# Sheet1.net
KiCad netlist of a schematic drawn in Altium Designer
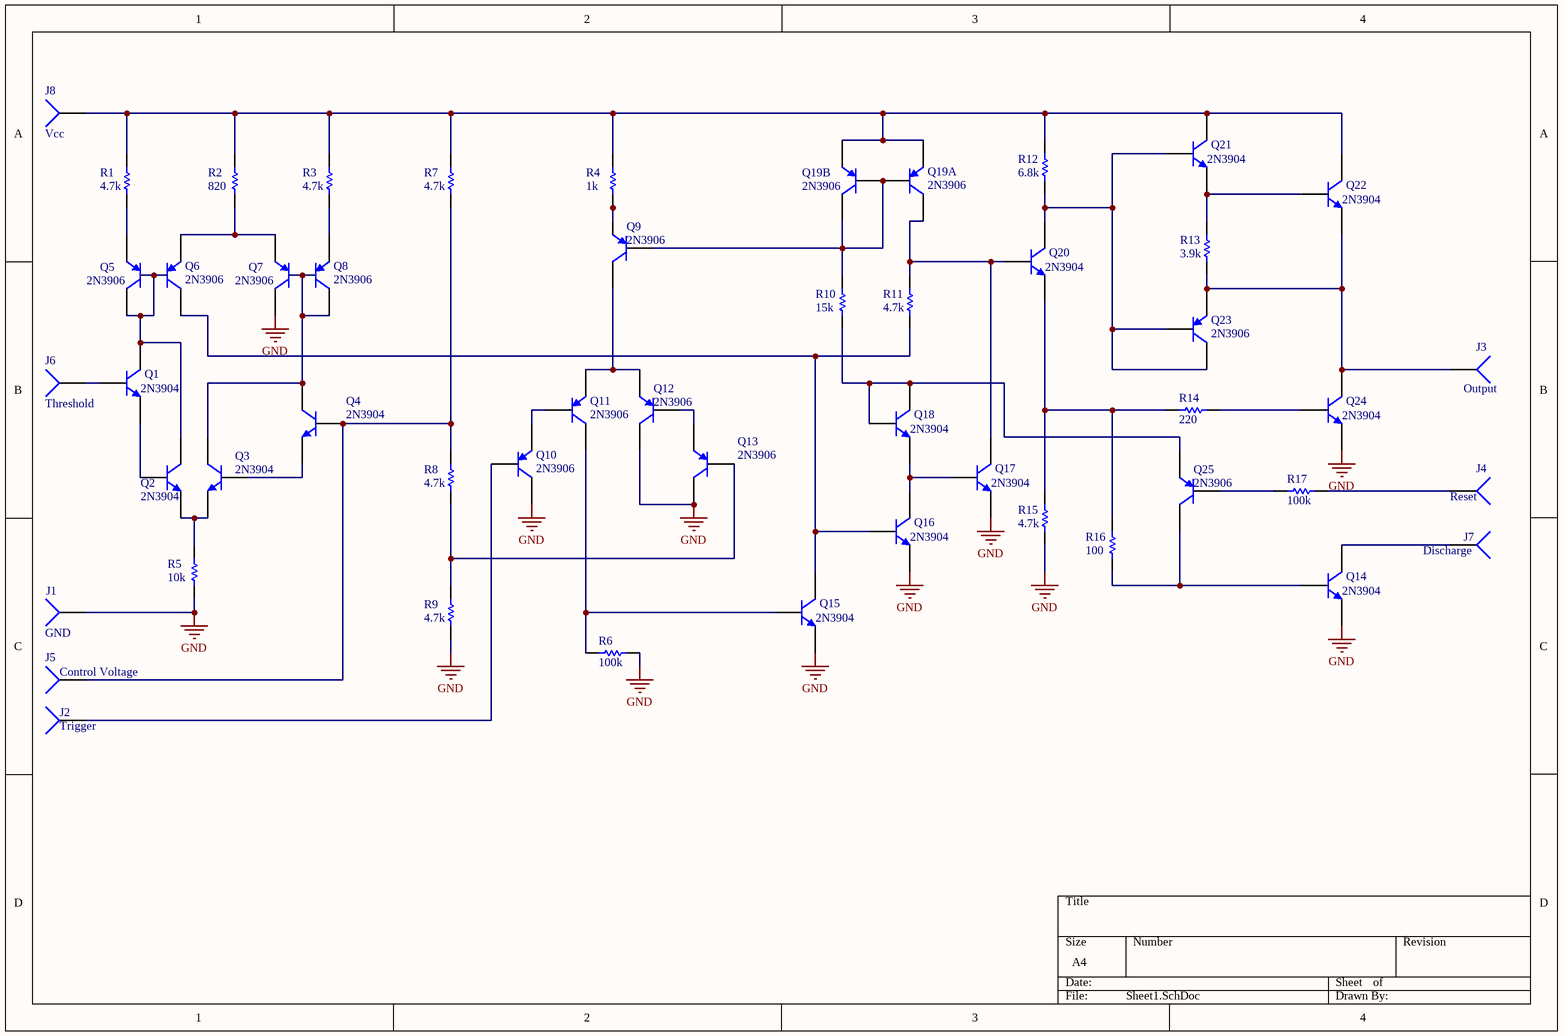
[diagram p0: Sheet1.SchDoc]

(export (version "E")
  (design (tool "Eeschema 10.0.6"))
  (components
    (comp (ref "J1")
      (value "GND")
      (footprint "PIN1")
      (description "Socket")
      (fields (field (name "PUBLISHER") "Altium Limited"))
      (libsource (lib "Miscellaneous Connectors") (part "Socket"))
    )
    (comp (ref "J2")
      (value "Trigger")
      (footprint "PIN1")
      (description "Socket")
      (fields (field (name "PUBLISHER") "Altium Limited"))
      (libsource (lib "Miscellaneous Connectors") (part "Socket"))
    )
    (comp (ref "J3")
      (value "Output")
      (footprint "PIN1")
      (description "Socket")
      (fields (field (name "PUBLISHER") "Altium Limited"))
      (libsource (lib "Miscellaneous Connectors") (part "Socket"))
    )
    (comp (ref "J4")
      (value "Reset")
      (footprint "PIN1")
      (description "Socket")
      (fields (field (name "PUBLISHER") "Altium Limited"))
      (libsource (lib "Miscellaneous Connectors") (part "Socket"))
    )
    (comp (ref "J5")
      (value "Control Voltage")
      (footprint "PIN1")
      (description "Socket")
      (fields (field (name "PUBLISHER") "Altium Limited"))
      (libsource (lib "Miscellaneous Connectors") (part "Socket"))
    )
    (comp (ref "J6")
      (value "Threshold")
      (footprint "PIN1")
      (description "Socket")
      (fields (field (name "PUBLISHER") "Altium Limited"))
      (libsource (lib "Miscellaneous Connectors") (part "Socket"))
    )
    (comp (ref "J7")
      (value "Discharge")
      (footprint "PIN1")
      (description "Socket")
      (fields (field (name "PUBLISHER") "Altium Limited"))
      (libsource (lib "Miscellaneous Connectors") (part "Socket"))
    )
    (comp (ref "J8")
      (value "Vcc")
      (footprint "PIN1")
      (description "Socket")
      (fields (field (name "PUBLISHER") "Altium Limited"))
      (libsource (lib "Miscellaneous Connectors") (part "Socket"))
    )
    (comp (ref "Q1")
      (value "2N3904")
      (footprint "TO-92A")
      (description "NPN General Purpose Amplifier")
      (fields (field (name "PUBLISHER") "Altium Limited"))
      (libsource (lib "Miscellaneous Devices") (part "2N3904"))
    )
    (comp (ref "Q2")
      (value "2N3904")
      (footprint "TO-92A")
      (description "NPN General Purpose Amplifier")
      (fields (field (name "PUBLISHER") "Altium Limited"))
      (libsource (lib "Miscellaneous Devices") (part "2N3904"))
    )
    (comp (ref "Q3")
      (value "2N3904")
      (footprint "TO-92A")
      (description "NPN General Purpose Amplifier")
      (fields (field (name "PUBLISHER") "Altium Limited"))
      (libsource (lib "Miscellaneous Devices") (part "2N3904"))
    )
    (comp (ref "Q4")
      (value "2N3904")
      (footprint "TO-92A")
      (description "NPN General Purpose Amplifier")
      (fields (field (name "PUBLISHER") "Altium Limited"))
      (libsource (lib "Miscellaneous Devices") (part "2N3904"))
    )
    (comp (ref "Q5")
      (value "2N3906")
      (footprint "TO-92A")
      (description "PNP General Purpose Amplifier")
      (fields (field (name "PUBLISHER") "Altium Limited"))
      (libsource (lib "Miscellaneous Devices") (part "2N3906"))
    )
    (comp (ref "Q6")
      (value "2N3906")
      (footprint "TO-92A")
      (description "PNP General Purpose Amplifier")
      (fields (field (name "PUBLISHER") "Altium Limited"))
      (libsource (lib "Miscellaneous Devices") (part "2N3906"))
    )
    (comp (ref "Q7")
      (value "2N3906")
      (footprint "TO-92A")
      (description "PNP General Purpose Amplifier")
      (fields (field (name "PUBLISHER") "Altium Limited"))
      (libsource (lib "Miscellaneous Devices") (part "2N3906"))
    )
    (comp (ref "Q8")
      (value "2N3906")
      (footprint "TO-92A")
      (description "PNP General Purpose Amplifier")
      (fields (field (name "PUBLISHER") "Altium Limited"))
      (libsource (lib "Miscellaneous Devices") (part "2N3906"))
    )
    (comp (ref "Q9")
      (value "2N3906")
      (footprint "TO-92A")
      (description "PNP General Purpose Amplifier")
      (fields (field (name "PUBLISHER") "Altium Limited"))
      (libsource (lib "Miscellaneous Devices") (part "2N3906"))
    )
    (comp (ref "Q10")
      (value "2N3906")
      (footprint "TO-92A")
      (description "PNP General Purpose Amplifier")
      (fields (field (name "PUBLISHER") "Altium Limited"))
      (libsource (lib "Miscellaneous Devices") (part "2N3906"))
    )
    (comp (ref "Q11")
      (value "2N3906")
      (footprint "TO-92A")
      (description "PNP General Purpose Amplifier")
      (fields (field (name "PUBLISHER") "Altium Limited"))
      (libsource (lib "Miscellaneous Devices") (part "2N3906"))
    )
    (comp (ref "Q12")
      (value "2N3906")
      (footprint "TO-92A")
      (description "PNP General Purpose Amplifier")
      (fields (field (name "PUBLISHER") "Altium Limited"))
      (libsource (lib "Miscellaneous Devices") (part "2N3906"))
    )
    (comp (ref "Q13")
      (value "2N3906")
      (footprint "TO-92A")
      (description "PNP General Purpose Amplifier")
      (fields (field (name "PUBLISHER") "Altium Limited"))
      (libsource (lib "Miscellaneous Devices") (part "2N3906"))
    )
    (comp (ref "Q14")
      (value "2N3904")
      (footprint "TO-92A")
      (description "NPN General Purpose Amplifier")
      (fields (field (name "PUBLISHER") "Altium Limited"))
      (libsource (lib "Miscellaneous Devices") (part "2N3904"))
    )
    (comp (ref "Q15")
      (value "2N3904")
      (footprint "TO-92A")
      (description "NPN General Purpose Amplifier")
      (fields (field (name "PUBLISHER") "Altium Limited"))
      (libsource (lib "Miscellaneous Devices") (part "2N3904"))
    )
    (comp (ref "Q16")
      (value "2N3904")
      (footprint "TO-92A")
      (description "NPN General Purpose Amplifier")
      (fields (field (name "PUBLISHER") "Altium Limited"))
      (libsource (lib "Miscellaneous Devices") (part "2N3904"))
    )
    (comp (ref "Q17")
      (value "2N3904")
      (footprint "TO-92A")
      (description "NPN General Purpose Amplifier")
      (fields (field (name "PUBLISHER") "Altium Limited"))
      (libsource (lib "Miscellaneous Devices") (part "2N3904"))
    )
    (comp (ref "Q18")
      (value "2N3904")
      (footprint "TO-92A")
      (description "NPN General Purpose Amplifier")
      (fields (field (name "PUBLISHER") "Altium Limited"))
      (libsource (lib "Miscellaneous Devices") (part "2N3904"))
    )
    (comp (ref "Q19A")
      (value "2N3906")
      (footprint "TO-92A")
      (description "PNP General Purpose Amplifier")
      (fields (field (name "PUBLISHER") "Altium Limited"))
      (libsource (lib "Miscellaneous Devices") (part "2N3906"))
    )
    (comp (ref "Q19B")
      (value "2N3906")
      (footprint "TO-92A")
      (description "PNP General Purpose Amplifier")
      (fields (field (name "PUBLISHER") "Altium Limited"))
      (libsource (lib "Miscellaneous Devices") (part "2N3906"))
    )
    (comp (ref "Q20")
      (value "2N3904")
      (footprint "TO-92A")
      (description "NPN General Purpose Amplifier")
      (fields (field (name "PUBLISHER") "Altium Limited"))
      (libsource (lib "Miscellaneous Devices") (part "2N3904"))
    )
    (comp (ref "Q21")
      (value "2N3904")
      (footprint "TO-92A")
      (description "NPN General Purpose Amplifier")
      (fields (field (name "PUBLISHER") "Altium Limited"))
      (libsource (lib "Miscellaneous Devices") (part "2N3904"))
    )
    (comp (ref "Q22")
      (value "2N3904")
      (footprint "TO-92A")
      (description "NPN General Purpose Amplifier")
      (fields (field (name "PUBLISHER") "Altium Limited"))
      (libsource (lib "Miscellaneous Devices") (part "2N3904"))
    )
    (comp (ref "Q23")
      (value "2N3906")
      (footprint "TO-92A")
      (description "PNP General Purpose Amplifier")
      (fields (field (name "PUBLISHER") "Altium Limited"))
      (libsource (lib "Miscellaneous Devices") (part "2N3906"))
    )
    (comp (ref "Q24")
      (value "2N3904")
      (footprint "TO-92A")
      (description "NPN General Purpose Amplifier")
      (fields (field (name "PUBLISHER") "Altium Limited"))
      (libsource (lib "Miscellaneous Devices") (part "2N3904"))
    )
    (comp (ref "Q25")
      (value "2N3906")
      (footprint "TO-92A")
      (description "PNP General Purpose Amplifier")
      (fields (field (name "PUBLISHER") "Altium Limited"))
      (libsource (lib "Miscellaneous Devices") (part "2N3906"))
    )
    (comp (ref "R1")
      (value "4.7k")
      (footprint "AXIAL-0.3")
      (description "Resistor")
      (fields (field (name "Comment") "Res1") (field (name "PUBLISHER") "Altium Limited"))
      (libsource (lib "Miscellaneous Devices") (part "Res1"))
    )
    (comp (ref "R2")
      (value "820")
      (footprint "AXIAL-0.3")
      (description "Resistor")
      (fields (field (name "Comment") "Res1") (field (name "PUBLISHER") "Altium Limited"))
      (libsource (lib "Miscellaneous Devices") (part "Res1"))
    )
    (comp (ref "R3")
      (value "4.7k")
      (footprint "AXIAL-0.3")
      (description "Resistor")
      (fields (field (name "Comment") "Res1") (field (name "PUBLISHER") "Altium Limited"))
      (libsource (lib "Miscellaneous Devices") (part "Res1"))
    )
    (comp (ref "R4")
      (value "1k")
      (footprint "AXIAL-0.3")
      (description "Resistor")
      (fields (field (name "Comment") "Res1") (field (name "PUBLISHER") "Altium Limited"))
      (libsource (lib "Miscellaneous Devices") (part "Res1"))
    )
    (comp (ref "R5")
      (value "10k")
      (footprint "AXIAL-0.3")
      (description "Resistor")
      (fields (field (name "Comment") "Res1") (field (name "PUBLISHER") "Altium Limited"))
      (libsource (lib "Miscellaneous Devices") (part "Res1"))
    )
    (comp (ref "R6")
      (value "100k")
      (footprint "AXIAL-0.3")
      (description "Resistor")
      (fields (field (name "Comment") "Res1") (field (name "PUBLISHER") "Altium Limited"))
      (libsource (lib "Miscellaneous Devices") (part "Res1"))
    )
    (comp (ref "R7")
      (value "4.7k")
      (footprint "AXIAL-0.3")
      (description "Resistor")
      (fields (field (name "Comment") "Res1") (field (name "PUBLISHER") "Altium Limited"))
      (libsource (lib "Miscellaneous Devices") (part "Res1"))
    )
    (comp (ref "R8")
      (value "4.7k")
      (footprint "AXIAL-0.3")
      (description "Resistor")
      (fields (field (name "Comment") "Res1") (field (name "PUBLISHER") "Altium Limited"))
      (libsource (lib "Miscellaneous Devices") (part "Res1"))
    )
    (comp (ref "R9")
      (value "4.7k")
      (footprint "AXIAL-0.3")
      (description "Resistor")
      (fields (field (name "Comment") "Res1") (field (name "PUBLISHER") "Altium Limited"))
      (libsource (lib "Miscellaneous Devices") (part "Res1"))
    )
    (comp (ref "R10")
      (value "15k")
      (footprint "AXIAL-0.3")
      (description "Resistor")
      (fields (field (name "Comment") "Res1") (field (name "PUBLISHER") "Altium Limited"))
      (libsource (lib "Miscellaneous Devices") (part "Res1"))
    )
    (comp (ref "R11")
      (value "4.7k")
      (footprint "AXIAL-0.3")
      (description "Resistor")
      (fields (field (name "Comment") "Res1") (field (name "PUBLISHER") "Altium Limited"))
      (libsource (lib "Miscellaneous Devices") (part "Res1"))
    )
    (comp (ref "R12")
      (value "6.8k")
      (footprint "AXIAL-0.3")
      (description "Resistor")
      (fields (field (name "Comment") "Res1") (field (name "PUBLISHER") "Altium Limited"))
      (libsource (lib "Miscellaneous Devices") (part "Res1"))
    )
    (comp (ref "R13")
      (value "3.9k")
      (footprint "AXIAL-0.3")
      (description "Resistor")
      (fields (field (name "Comment") "Res1") (field (name "PUBLISHER") "Altium Limited"))
      (libsource (lib "Miscellaneous Devices") (part "Res1"))
    )
    (comp (ref "R14")
      (value "220")
      (footprint "AXIAL-0.3")
      (description "Resistor")
      (fields (field (name "Comment") "Res1") (field (name "PUBLISHER") "Altium Limited"))
      (libsource (lib "Miscellaneous Devices") (part "Res1"))
    )
    (comp (ref "R15")
      (value "4.7k")
      (footprint "AXIAL-0.3")
      (description "Resistor")
      (fields (field (name "Comment") "Res1") (field (name "PUBLISHER") "Altium Limited"))
      (libsource (lib "Miscellaneous Devices") (part "Res1"))
    )
    (comp (ref "R16")
      (value "100")
      (footprint "AXIAL-0.3")
      (description "Resistor")
      (fields (field (name "Comment") "Res1") (field (name "PUBLISHER") "Altium Limited"))
      (libsource (lib "Miscellaneous Devices") (part "Res1"))
    )
    (comp (ref "R17")
      (value "100k")
      (footprint "AXIAL-0.3")
      (description "Resistor")
      (fields (field (name "Comment") "Res1") (field (name "PUBLISHER") "Altium Limited"))
      (libsource (lib "Miscellaneous Devices") (part "Res1"))
    )
  )
  (nets
    (net (code "1") (name "GND") (class "Default")
      (node (ref "J1") (pin "1") (pinfunction "1_1") (pintype "passive"))
      (node (ref "Q10") (pin "3") (pinfunction "C_3") (pintype "passive"))
      (node (ref "Q12") (pin "3") (pinfunction "C_3") (pintype "passive"))
      (node (ref "Q13") (pin "3") (pinfunction "C_3") (pintype "passive"))
      (node (ref "Q14") (pin "1") (pinfunction "E_1") (pintype "passive"))
      (node (ref "Q15") (pin "1") (pinfunction "E_1") (pintype "passive"))
      (node (ref "Q16") (pin "1") (pinfunction "E_1") (pintype "passive"))
      (node (ref "Q17") (pin "1") (pinfunction "E_1") (pintype "passive"))
      (node (ref "Q24") (pin "1") (pinfunction "E_1") (pintype "passive"))
      (node (ref "Q7") (pin "3") (pinfunction "C_3") (pintype "passive"))
      (node (ref "R15") (pin "1") (pinfunction "1_1") (pintype "passive"))
      (node (ref "R5") (pin "1") (pinfunction "1_1") (pintype "passive"))
      (node (ref "R6") (pin "1") (pinfunction "1_1") (pintype "passive"))
      (node (ref "R9") (pin "1") (pinfunction "1_1") (pintype "passive"))
    )
    (net (code "2") (name "Net-(J4-Pad1)") (class "Default")
      (node (ref "J4") (pin "1") (pinfunction "1_1") (pintype "passive"))
      (node (ref "R17") (pin "1") (pinfunction "1_1") (pintype "passive"))
    )
    (net (code "3") (name "Net-(Q1-B)") (class "Default")
      (node (ref "J6") (pin "1") (pinfunction "1_1") (pintype "passive"))
      (node (ref "Q1") (pin "2") (pinfunction "B_2") (pintype "passive"))
    )
    (net (code "4") (name "Net-(Q1-C)") (class "Default")
      (node (ref "Q1") (pin "3") (pinfunction "C_3") (pintype "passive"))
      (node (ref "Q2") (pin "3") (pinfunction "C_3") (pintype "passive"))
      (node (ref "Q5") (pin "2") (pinfunction "B_2") (pintype "passive"))
      (node (ref "Q5") (pin "3") (pinfunction "C_3") (pintype "passive"))
      (node (ref "Q6") (pin "2") (pinfunction "B_2") (pintype "passive"))
    )
    (net (code "5") (name "Net-(Q1-E)") (class "Default")
      (node (ref "Q1") (pin "1") (pinfunction "E_1") (pintype "passive"))
      (node (ref "Q2") (pin "2") (pinfunction "B_2") (pintype "passive"))
    )
    (net (code "6") (name "Net-(Q2-E)") (class "Default")
      (node (ref "Q2") (pin "1") (pinfunction "E_1") (pintype "passive"))
      (node (ref "Q3") (pin "1") (pinfunction "E_1") (pintype "passive"))
      (node (ref "R5") (pin "2") (pinfunction "2_2") (pintype "passive"))
    )
    (net (code "7") (name "Net-(Q3-B)") (class "Default")
      (node (ref "Q3") (pin "2") (pinfunction "B_2") (pintype "passive"))
      (node (ref "Q4") (pin "1") (pinfunction "E_1") (pintype "passive"))
    )
    (net (code "8") (name "Net-(Q3-C)") (class "Default")
      (node (ref "Q3") (pin "3") (pinfunction "C_3") (pintype "passive"))
      (node (ref "Q4") (pin "3") (pinfunction "C_3") (pintype "passive"))
      (node (ref "Q7") (pin "2") (pinfunction "B_2") (pintype "passive"))
      (node (ref "Q8") (pin "2") (pinfunction "B_2") (pintype "passive"))
      (node (ref "Q8") (pin "3") (pinfunction "C_3") (pintype "passive"))
    )
    (net (code "9") (name "Net-(Q4-B)") (class "Default")
      (node (ref "J5") (pin "1") (pinfunction "1_1") (pintype "passive"))
      (node (ref "Q4") (pin "2") (pinfunction "B_2") (pintype "passive"))
      (node (ref "R7") (pin "1") (pinfunction "1_1") (pintype "passive"))
      (node (ref "R8") (pin "2") (pinfunction "2_2") (pintype "passive"))
    )
    (net (code "10") (name "Net-(Q5-E)") (class "Default")
      (node (ref "Q5") (pin "1") (pinfunction "E_1") (pintype "passive"))
      (node (ref "R1") (pin "1") (pinfunction "1_1") (pintype "passive"))
    )
    (net (code "11") (name "Net-(Q6-E)") (class "Default")
      (node (ref "Q6") (pin "1") (pinfunction "E_1") (pintype "passive"))
      (node (ref "Q7") (pin "1") (pinfunction "E_1") (pintype "passive"))
      (node (ref "R2") (pin "1") (pinfunction "1_1") (pintype "passive"))
    )
    (net (code "12") (name "Net-(Q8-E)") (class "Default")
      (node (ref "Q8") (pin "1") (pinfunction "E_1") (pintype "passive"))
      (node (ref "R3") (pin "1") (pinfunction "1_1") (pintype "passive"))
    )
    (net (code "13") (name "Net-(Q9-E)") (class "Default")
      (node (ref "Q9") (pin "1") (pinfunction "E_1") (pintype "passive"))
      (node (ref "R4") (pin "1") (pinfunction "1_1") (pintype "passive"))
    )
    (net (code "14") (name "Net-(Q10-B)") (class "Default")
      (node (ref "J2") (pin "1") (pinfunction "1_1") (pintype "passive"))
      (node (ref "Q10") (pin "2") (pinfunction "B_2") (pintype "passive"))
    )
    (net (code "15") (name "Net-(Q10-E)") (class "Default")
      (node (ref "Q10") (pin "1") (pinfunction "E_1") (pintype "passive"))
      (node (ref "Q11") (pin "2") (pinfunction "B_2") (pintype "passive"))
    )
    (net (code "16") (name "Net-(Q11-C)") (class "Default")
      (node (ref "Q11") (pin "3") (pinfunction "C_3") (pintype "passive"))
      (node (ref "Q15") (pin "2") (pinfunction "B_2") (pintype "passive"))
      (node (ref "R6") (pin "2") (pinfunction "2_2") (pintype "passive"))
    )
    (net (code "17") (name "Net-(Q11-E)") (class "Default")
      (node (ref "Q11") (pin "1") (pinfunction "E_1") (pintype "passive"))
      (node (ref "Q12") (pin "1") (pinfunction "E_1") (pintype "passive"))
      (node (ref "Q9") (pin "3") (pinfunction "C_3") (pintype "passive"))
    )
    (net (code "18") (name "Net-(Q12-B)") (class "Default")
      (node (ref "Q12") (pin "2") (pinfunction "B_2") (pintype "passive"))
      (node (ref "Q13") (pin "1") (pinfunction "E_1") (pintype "passive"))
    )
    (net (code "19") (name "Net-(Q13-B)") (class "Default")
      (node (ref "Q13") (pin "2") (pinfunction "B_2") (pintype "passive"))
      (node (ref "R8") (pin "1") (pinfunction "1_1") (pintype "passive"))
      (node (ref "R9") (pin "2") (pinfunction "2_2") (pintype "passive"))
    )
    (net (code "20") (name "Net-(Q14-B)") (class "Default")
      (node (ref "Q14") (pin "2") (pinfunction "B_2") (pintype "passive"))
      (node (ref "Q25") (pin "3") (pinfunction "C_3") (pintype "passive"))
      (node (ref "R16") (pin "1") (pinfunction "1_1") (pintype "passive"))
    )
    (net (code "21") (name "Net-(Q14-C)") (class "Default")
      (node (ref "J7") (pin "1") (pinfunction "1_1") (pintype "passive"))
      (node (ref "Q14") (pin "3") (pinfunction "C_3") (pintype "passive"))
    )
    (net (code "22") (name "Net-(Q15-C)") (class "Default")
      (node (ref "Q15") (pin "3") (pinfunction "C_3") (pintype "passive"))
      (node (ref "Q16") (pin "2") (pinfunction "B_2") (pintype "passive"))
      (node (ref "Q6") (pin "3") (pinfunction "C_3") (pintype "passive"))
      (node (ref "R11") (pin "1") (pinfunction "1_1") (pintype "passive"))
    )
    (net (code "23") (name "Net-(Q16-C)") (class "Default")
      (node (ref "Q16") (pin "3") (pinfunction "C_3") (pintype "passive"))
      (node (ref "Q17") (pin "2") (pinfunction "B_2") (pintype "passive"))
      (node (ref "Q18") (pin "1") (pinfunction "E_1") (pintype "passive"))
    )
    (net (code "24") (name "Net-(Q17-C)") (class "Default")
      (node (ref "Q17") (pin "3") (pinfunction "C_3") (pintype "passive"))
      (node (ref "Q19A") (pin "3") (pinfunction "C_3") (pintype "passive"))
      (node (ref "Q20") (pin "2") (pinfunction "B_2") (pintype "passive"))
      (node (ref "R11") (pin "2") (pinfunction "2_2") (pintype "passive"))
    )
    (net (code "25") (name "Net-(Q18-B)") (class "Default")
      (node (ref "Q18") (pin "2") (pinfunction "B_2") (pintype "passive"))
      (node (ref "Q18") (pin "3") (pinfunction "C_3") (pintype "passive"))
      (node (ref "Q25") (pin "1") (pinfunction "E_1") (pintype "passive"))
      (node (ref "R10") (pin "1") (pinfunction "1_1") (pintype "passive"))
    )
    (net (code "26") (name "Net-(Q19A-B)") (class "Default")
      (node (ref "Q19A") (pin "2") (pinfunction "B_2") (pintype "passive"))
      (node (ref "Q19B") (pin "2") (pinfunction "B_2") (pintype "passive"))
      (node (ref "Q19B") (pin "3") (pinfunction "C_3") (pintype "passive"))
      (node (ref "Q9") (pin "2") (pinfunction "B_2") (pintype "passive"))
      (node (ref "R10") (pin "2") (pinfunction "2_2") (pintype "passive"))
    )
    (net (code "27") (name "Net-(Q19A-E)") (class "Default")
      (node (ref "J8") (pin "1") (pinfunction "1_1") (pintype "passive"))
      (node (ref "Q19A") (pin "1") (pinfunction "E_1") (pintype "passive"))
      (node (ref "Q19B") (pin "1") (pinfunction "E_1") (pintype "passive"))
      (node (ref "Q21") (pin "3") (pinfunction "C_3") (pintype "passive"))
      (node (ref "Q22") (pin "3") (pinfunction "C_3") (pintype "passive"))
      (node (ref "R1") (pin "2") (pinfunction "2_2") (pintype "passive"))
      (node (ref "R12") (pin "2") (pinfunction "2_2") (pintype "passive"))
      (node (ref "R2") (pin "2") (pinfunction "2_2") (pintype "passive"))
      (node (ref "R3") (pin "2") (pinfunction "2_2") (pintype "passive"))
      (node (ref "R4") (pin "2") (pinfunction "2_2") (pintype "passive"))
      (node (ref "R7") (pin "2") (pinfunction "2_2") (pintype "passive"))
    )
    (net (code "28") (name "Net-(Q20-C)") (class "Default")
      (node (ref "Q20") (pin "3") (pinfunction "C_3") (pintype "passive"))
      (node (ref "Q21") (pin "2") (pinfunction "B_2") (pintype "passive"))
      (node (ref "Q23") (pin "2") (pinfunction "B_2") (pintype "passive"))
      (node (ref "Q23") (pin "3") (pinfunction "C_3") (pintype "passive"))
      (node (ref "R12") (pin "1") (pinfunction "1_1") (pintype "passive"))
    )
    (net (code "29") (name "Net-(Q20-E)") (class "Default")
      (node (ref "Q20") (pin "1") (pinfunction "E_1") (pintype "passive"))
      (node (ref "R14") (pin "2") (pinfunction "2_2") (pintype "passive"))
      (node (ref "R15") (pin "2") (pinfunction "2_2") (pintype "passive"))
      (node (ref "R16") (pin "2") (pinfunction "2_2") (pintype "passive"))
    )
    (net (code "30") (name "Net-(Q21-E)") (class "Default")
      (node (ref "Q21") (pin "1") (pinfunction "E_1") (pintype "passive"))
      (node (ref "Q22") (pin "2") (pinfunction "B_2") (pintype "passive"))
      (node (ref "R13") (pin "2") (pinfunction "2_2") (pintype "passive"))
    )
    (net (code "31") (name "Net-(Q22-E)") (class "Default")
      (node (ref "J3") (pin "1") (pinfunction "1_1") (pintype "passive"))
      (node (ref "Q22") (pin "1") (pinfunction "E_1") (pintype "passive"))
      (node (ref "Q23") (pin "1") (pinfunction "E_1") (pintype "passive"))
      (node (ref "Q24") (pin "3") (pinfunction "C_3") (pintype "passive"))
      (node (ref "R13") (pin "1") (pinfunction "1_1") (pintype "passive"))
    )
    (net (code "32") (name "Net-(Q24-B)") (class "Default")
      (node (ref "Q24") (pin "2") (pinfunction "B_2") (pintype "passive"))
      (node (ref "R14") (pin "1") (pinfunction "1_1") (pintype "passive"))
    )
    (net (code "33") (name "Net-(Q25-B)") (class "Default")
      (node (ref "Q25") (pin "2") (pinfunction "B_2") (pintype "passive"))
      (node (ref "R17") (pin "2") (pinfunction "2_2") (pintype "passive"))
    )
  )
)
